# Rx_power.net
KiCad netlist of a schematic drawn in Altium Designer
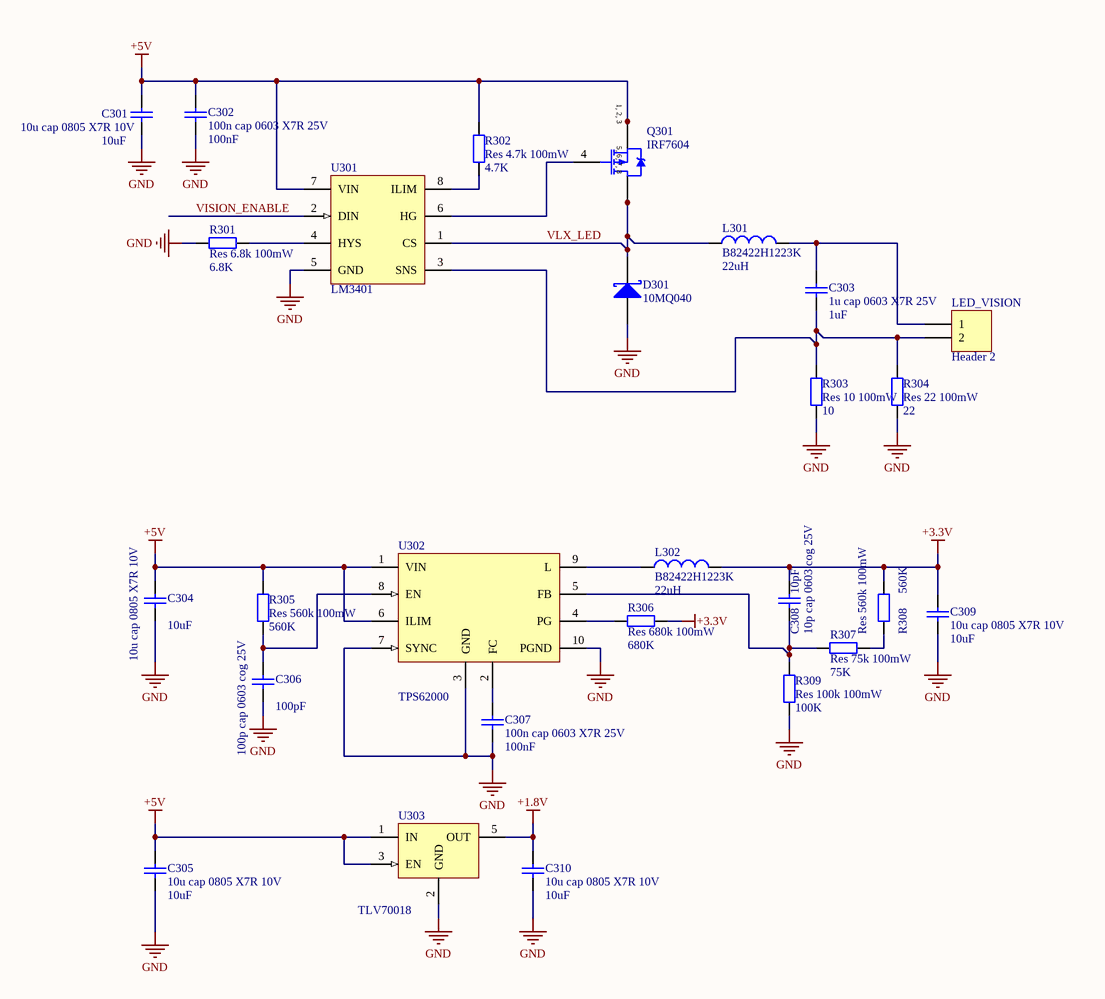
[diagram p0: Rx_power.SchDoc]

(export (version "E")
  (design (tool "Eeschema 10.0.6"))
  (components
    (comp (ref "C301")
      (value "10u cap 0805 X7R 10V")
      (footprint "0805")
      (description "Capacitor")
      (fields (field (name "ALTIUM_VALUE") "10uF") (field (name "PUBLISHER") "Altium Limited"))
      (libsource (lib "Miscellaneous Devices") (part "Cap"))
    )
    (comp (ref "C302")
      (value "100n cap 0603 X7R 25V")
      (footprint "0603")
      (description "Capacitor")
      (fields (field (name "ALTIUM_VALUE") "100nF") (field (name "PUBLISHER") "Altium Limited"))
      (libsource (lib "Miscellaneous Devices") (part "Cap"))
    )
    (comp (ref "C303")
      (value "1u cap 0603 X7R 25V")
      (footprint "0603")
      (description "Capacitor")
      (fields (field (name "ALTIUM_VALUE") "1uF") (field (name "PUBLISHER") "Altium Limited"))
      (libsource (lib "Miscellaneous Devices") (part "Cap"))
    )
    (comp (ref "C304")
      (value "10u cap 0805 X7R 10V")
      (footprint "0805")
      (description "Capacitor")
      (fields (field (name "ALTIUM_VALUE") "10uF") (field (name "PUBLISHER") "Altium Limited"))
      (libsource (lib "Miscellaneous Devices") (part "Cap"))
    )
    (comp (ref "C305")
      (value "10u cap 0805 X7R 10V")
      (footprint "0805")
      (description "Capacitor")
      (fields (field (name "ALTIUM_VALUE") "10uF") (field (name "PUBLISHER") "Altium Limited"))
      (libsource (lib "Miscellaneous Devices") (part "Cap"))
    )
    (comp (ref "C306")
      (value "100p cap 0603 cog 25V")
      (footprint "0603")
      (description "Capacitor")
      (fields (field (name "ALTIUM_VALUE") "100pF") (field (name "PUBLISHER") "Altium Limited"))
      (libsource (lib "Miscellaneous Devices") (part "Cap"))
    )
    (comp (ref "C307")
      (value "100n cap 0603 X7R 25V")
      (footprint "0603")
      (description "Capacitor")
      (fields (field (name "ALTIUM_VALUE") "100nF") (field (name "PUBLISHER") "Altium Limited"))
      (libsource (lib "Miscellaneous Devices") (part "Cap"))
    )
    (comp (ref "C308")
      (value "10p cap 0603 cog 25V")
      (footprint "0603")
      (description "Capacitor")
      (fields (field (name "ALTIUM_VALUE") "10pF") (field (name "PUBLISHER") "Altium Limited"))
      (libsource (lib "Miscellaneous Devices") (part "Cap"))
    )
    (comp (ref "C309")
      (value "10u cap 0805 X7R 10V")
      (footprint "0805")
      (description "Capacitor")
      (fields (field (name "ALTIUM_VALUE") "10uF") (field (name "PUBLISHER") "Altium Limited"))
      (libsource (lib "Miscellaneous Devices") (part "Cap"))
    )
    (comp (ref "C310")
      (value "10u cap 0805 X7R 10V")
      (footprint "0805")
      (description "Capacitor")
      (fields (field (name "ALTIUM_VALUE") "10uF") (field (name "PUBLISHER") "Altium Limited"))
      (libsource (lib "Miscellaneous Devices") (part "Cap"))
    )
    (comp (ref "D301")
      (value "10MQ040")
      (footprint "D-64")
      (description "Schottky Rectifier")
      (fields (field (name "PUBLISHER") "Altium Limited"))
      (libsource (lib "IR Rectifier - Schottky") (part "10MQ040"))
    )
    (comp (ref "L301")
      (value "B82422H1223K")
      (footprint "1210")
      (description "Inductor")
      (fields (field (name "ALTIUM_VALUE") "22uH") (field (name "PUBLISHER") "Altium Limited"))
      (libsource (lib "Miscellaneous Devices") (part "Inductor"))
    )
    (comp (ref "L302")
      (value "B82422H1223K")
      (footprint "1210")
      (description "Inductor")
      (fields (field (name "ALTIUM_VALUE") "22uH") (field (name "PUBLISHER") "Altium Limited"))
      (libsource (lib "Miscellaneous Devices") (part "Inductor"))
    )
    (comp (ref "LED_VISION")
      (value "Header 2")
      (footprint "HDR1X2")
      (description "Header, 2-Pin")
      (fields (field (name "PUBLISHER") "Altium Limited"))
      (libsource (lib "Miscellaneous Connectors") (part "Header 2"))
    )
    (comp (ref "Q301")
      (value "IRF7604")
      (footprint "Micro8")
      (description "HEXFET Power MOSFET")
      (fields (field (name "PUBLISHER") "Altium Limited"))
      (libsource (lib "IR Discrete MOSFET - Power") (part "IRF7604"))
    )
    (comp (ref "R301")
      (value "Res 6.8k 100mW")
      (footprint "0603")
      (description "Resistor")
      (fields (field (name "ALTIUM_VALUE") "6.8K") (field (name "PUBLISHER") "Altium Limited"))
      (libsource (lib "Miscellaneous Devices") (part "Res2"))
    )
    (comp (ref "R302")
      (value "Res 4.7k 100mW")
      (footprint "0603")
      (description "Resistor")
      (fields (field (name "ALTIUM_VALUE") "4.7K") (field (name "PUBLISHER") "Altium Limited"))
      (libsource (lib "") (part "Res2_1"))
    )
    (comp (ref "R303")
      (value "Res 10 100mW")
      (footprint "0603")
      (description "Resistor")
      (fields (field (name "ALTIUM_VALUE") "10") (field (name "PUBLISHER") "Altium Limited"))
      (libsource (lib "") (part "Res2_1"))
    )
    (comp (ref "R304")
      (value "Res 22 100mW")
      (footprint "0603")
      (description "Resistor")
      (fields (field (name "ALTIUM_VALUE") "22") (field (name "PUBLISHER") "Altium Limited"))
      (libsource (lib "") (part "Res2_1"))
    )
    (comp (ref "R305")
      (value "Res 560k 100mW")
      (footprint "0603")
      (description "Resistor")
      (fields (field (name "ALTIUM_VALUE") "560K") (field (name "PUBLISHER") "Altium Limited"))
      (libsource (lib "") (part "Res2_1"))
    )
    (comp (ref "R306")
      (value "Res 680k 100mW")
      (footprint "0603")
      (description "Resistor")
      (fields (field (name "ALTIUM_VALUE") "680K") (field (name "PUBLISHER") "Altium Limited"))
      (libsource (lib "Miscellaneous Devices") (part "Res2"))
    )
    (comp (ref "R307")
      (value "Res 75k 100mW")
      (footprint "0603")
      (description "Resistor")
      (fields (field (name "ALTIUM_VALUE") "75K") (field (name "PUBLISHER") "Altium Limited"))
      (libsource (lib "Miscellaneous Devices") (part "Res2"))
    )
    (comp (ref "R308")
      (value "Res 560k 100mW")
      (footprint "0603")
      (description "Resistor")
      (fields (field (name "ALTIUM_VALUE") "560K") (field (name "PUBLISHER") "Altium Limited"))
      (libsource (lib "") (part "Res2_1"))
    )
    (comp (ref "R309")
      (value "Res 100k 100mW")
      (footprint "0603")
      (description "Resistor")
      (fields (field (name "ALTIUM_VALUE") "100K") (field (name "PUBLISHER") "Altium Limited"))
      (libsource (lib "") (part "Res2_1"))
    )
    (comp (ref "U301")
      (value "LM3401")
      (footprint "MSOP8")
      (description "Hysteretic PFET Controller for High Power LED Drive")
      (libsource (lib "Oufff_Lib2") (part "LM3401"))
    )
    (comp (ref "U302")
      (value "TPS62000")
      (footprint "MS10")
      (description "HIGH-EFFICIENCY STEP-DOWN LOW POWER DC-DC CONVERTER")
      (libsource (lib "Oufff_Lib2") (part "TPS6200x"))
    )
    (comp (ref "U303")
      (value "TLV70018")
      (footprint "SOT23-5")
      (description "200-mA, Low-IQ, Low-Dropout Regulator for Portable Devices")
      (libsource (lib "Oufff_Lib2") (part "TLV700xx"))
    )
  )
  (nets
    (net (code "1") (name "+1.8V") (class "Default")
      (node (ref "C310") (pin "2") (pinfunction "2_2") (pintype "passive"))
      (node (ref "U303") (pin "5") (pinfunction "OUT_5") (pintype "power_in"))
    )
    (net (code "2") (name "+3.3V") (class "Default")
      (node (ref "C308") (pin "2") (pinfunction "2_2") (pintype "passive"))
      (node (ref "C309") (pin "2") (pinfunction "2_2") (pintype "passive"))
      (node (ref "L302") (pin "2") (pinfunction "2_2") (pintype "passive"))
      (node (ref "R306") (pin "2") (pinfunction "2_2") (pintype "passive"))
      (node (ref "R308") (pin "2") (pinfunction "2_2") (pintype "passive"))
    )
    (net (code "3") (name "+5V") (class "Default")
      (node (ref "C301") (pin "2") (pinfunction "2_2") (pintype "passive"))
      (node (ref "C302") (pin "2") (pinfunction "2_2") (pintype "passive"))
      (node (ref "C304") (pin "2") (pinfunction "2_2") (pintype "passive"))
      (node (ref "C305") (pin "2") (pinfunction "2_2") (pintype "passive"))
      (node (ref "Q301") (pin "1") (pinfunction "S_1") (pintype "passive"))
      (node (ref "Q301") (pin "2") (pinfunction "S_2") (pintype "passive"))
      (node (ref "Q301") (pin "3") (pinfunction "S_3") (pintype "passive"))
      (node (ref "R302") (pin "2") (pinfunction "2_2") (pintype "passive"))
      (node (ref "R305") (pin "2") (pinfunction "2_2") (pintype "passive"))
      (node (ref "U301") (pin "7") (pinfunction "VIN_7") (pintype "power_in"))
      (node (ref "U302") (pin "1") (pinfunction "VIN_1") (pintype "power_in"))
      (node (ref "U302") (pin "6") (pinfunction "ILIM_6") (pintype "passive"))
      (node (ref "U303") (pin "1") (pinfunction "IN_1") (pintype "power_in"))
      (node (ref "U303") (pin "3") (pinfunction "EN_3") (pintype "input"))
    )
    (net (code "4") (name "/VISION_ENABLE") (class "Default")
      (node (ref "U301") (pin "2") (pinfunction "DIN_2") (pintype "input"))
    )
    (net (code "5") (name "/VLX_LED") (class "Default")
      (node (ref "D301") (pin "2") (pinfunction "K_2") (pintype "passive"))
      (node (ref "L301") (pin "1") (pinfunction "1_1") (pintype "passive"))
      (node (ref "Q301") (pin "5") (pinfunction "D_5") (pintype "passive"))
      (node (ref "Q301") (pin "6") (pinfunction "D_6") (pintype "passive"))
      (node (ref "Q301") (pin "7") (pinfunction "D_7") (pintype "passive"))
      (node (ref "Q301") (pin "8") (pinfunction "D_8") (pintype "passive"))
      (node (ref "U301") (pin "1") (pinfunction "CS_1") (pintype "passive"))
    )
    (net (code "6") (name "GND") (class "Default")
      (node (ref "C301") (pin "1") (pinfunction "1_1") (pintype "passive"))
      (node (ref "C302") (pin "1") (pinfunction "1_1") (pintype "passive"))
      (node (ref "C304") (pin "1") (pinfunction "1_1") (pintype "passive"))
      (node (ref "C305") (pin "1") (pinfunction "1_1") (pintype "passive"))
      (node (ref "C306") (pin "1") (pinfunction "1_1") (pintype "passive"))
      (node (ref "C307") (pin "1") (pinfunction "1_1") (pintype "passive"))
      (node (ref "C309") (pin "1") (pinfunction "1_1") (pintype "passive"))
      (node (ref "C310") (pin "1") (pinfunction "1_1") (pintype "passive"))
      (node (ref "D301") (pin "1") (pinfunction "A_1") (pintype "passive"))
      (node (ref "R301") (pin "1") (pinfunction "1_1") (pintype "passive"))
      (node (ref "R303") (pin "1") (pinfunction "1_1") (pintype "passive"))
      (node (ref "R304") (pin "1") (pinfunction "1_1") (pintype "passive"))
      (node (ref "R309") (pin "1") (pinfunction "1_1") (pintype "passive"))
      (node (ref "U301") (pin "5") (pinfunction "GND_5") (pintype "power_in"))
      (node (ref "U302") (pin "10") (pinfunction "PGND_10") (pintype "power_in"))
      (node (ref "U302") (pin "3") (pinfunction "GND_3") (pintype "power_in"))
      (node (ref "U302") (pin "7") (pinfunction "SYNC_7") (pintype "input"))
      (node (ref "U303") (pin "2") (pinfunction "GND_2") (pintype "power_in"))
    )
    (net (code "7") (name "Net-(C303-Pad2)") (class "Default")
      (node (ref "C303") (pin "2") (pinfunction "2_2") (pintype "passive"))
      (node (ref "L301") (pin "2") (pinfunction "2_2") (pintype "passive"))
      (node (ref "LED_VISION") (pin "1") (pinfunction "1_1") (pintype "passive"))
    )
    (net (code "8") (name "Net-(Q301-G)") (class "Default")
      (node (ref "Q301") (pin "4") (pinfunction "G_4") (pintype "passive"))
      (node (ref "U301") (pin "6") (pinfunction "HG_6") (pintype "passive"))
    )
    (net (code "9") (name "Net-(R307-Pad2)") (class "Default")
      (node (ref "R307") (pin "2") (pinfunction "2_2") (pintype "passive"))
      (node (ref "R308") (pin "1") (pinfunction "1_1") (pintype "passive"))
    )
    (net (code "10") (name "Net-(U301-HYS)") (class "Default")
      (node (ref "R301") (pin "2") (pinfunction "2_2") (pintype "passive"))
      (node (ref "U301") (pin "4") (pinfunction "HYS_4") (pintype "passive"))
    )
    (net (code "11") (name "Net-(U301-ILIM)") (class "Default")
      (node (ref "R302") (pin "1") (pinfunction "1_1") (pintype "passive"))
      (node (ref "U301") (pin "8") (pinfunction "ILIM_8") (pintype "passive"))
    )
    (net (code "12") (name "Net-(U301-SNS)") (class "Default")
      (node (ref "C303") (pin "1") (pinfunction "1_1") (pintype "passive"))
      (node (ref "LED_VISION") (pin "2") (pinfunction "2_2") (pintype "passive"))
      (node (ref "R303") (pin "2") (pinfunction "2_2") (pintype "passive"))
      (node (ref "R304") (pin "2") (pinfunction "2_2") (pintype "passive"))
      (node (ref "U301") (pin "3") (pinfunction "SNS_3") (pintype "passive"))
    )
    (net (code "13") (name "Net-(U302-EN)") (class "Default")
      (node (ref "C306") (pin "2") (pinfunction "2_2") (pintype "passive"))
      (node (ref "R305") (pin "1") (pinfunction "1_1") (pintype "passive"))
      (node (ref "U302") (pin "8") (pinfunction "EN_8") (pintype "input"))
    )
    (net (code "14") (name "Net-(U302-FB)") (class "Default")
      (node (ref "C308") (pin "1") (pinfunction "1_1") (pintype "passive"))
      (node (ref "R307") (pin "1") (pinfunction "1_1") (pintype "passive"))
      (node (ref "R309") (pin "2") (pinfunction "2_2") (pintype "passive"))
      (node (ref "U302") (pin "5") (pinfunction "FB_5") (pintype "passive"))
    )
    (net (code "15") (name "Net-(U302-FC)") (class "Default")
      (node (ref "C307") (pin "2") (pinfunction "2_2") (pintype "passive"))
      (node (ref "U302") (pin "2") (pinfunction "FC_2") (pintype "passive"))
    )
    (net (code "16") (name "Net-(U302-L)") (class "Default")
      (node (ref "L302") (pin "1") (pinfunction "1_1") (pintype "passive"))
      (node (ref "U302") (pin "9") (pinfunction "L_9") (pintype "power_in"))
    )
    (net (code "17") (name "Net-(U302-PG)") (class "Default")
      (node (ref "R306") (pin "1") (pinfunction "1_1") (pintype "passive"))
      (node (ref "U302") (pin "4") (pinfunction "PG_4") (pintype "open_collector"))
    )
  )
)
